# powersupppy.net
KiCad netlist of a schematic drawn in EAGLE
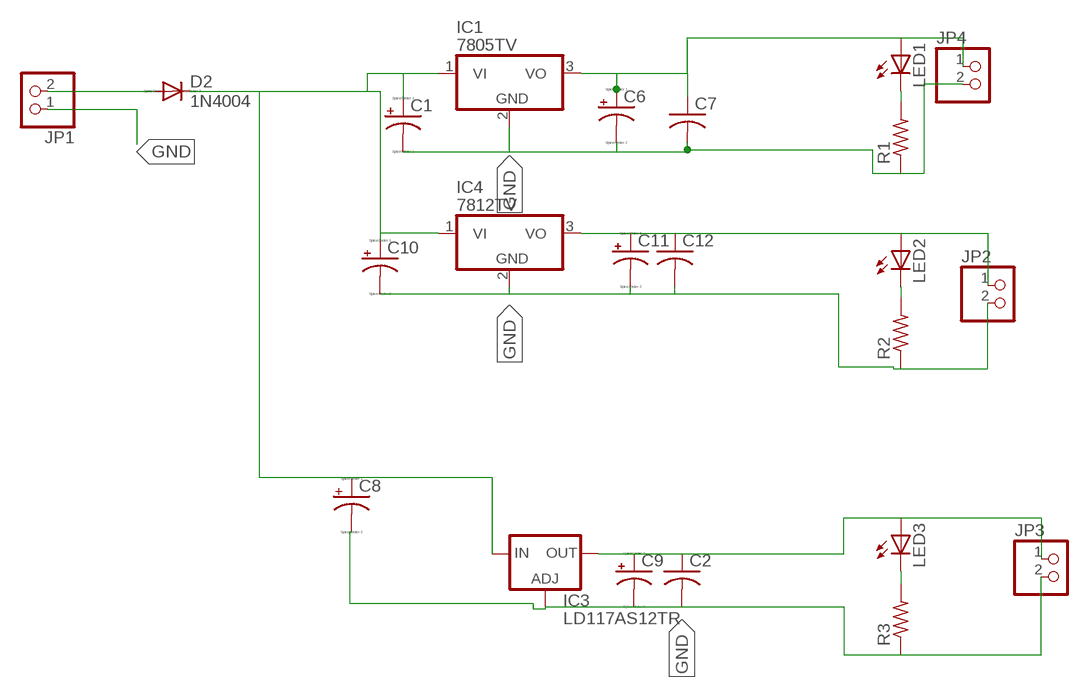
[diagram p0: schematic, sheet 1]

(export (version "E")
  (design (tool "Eeschema 10.0.6"))
  (components
    (comp (ref "C1")
      (value "CPOL-USE2.5-5")
      (footprint "eagle-import:E2,5-5")
      (libsource (lib "eagle-import") (part "CPOL-USE2.5-5"))
    )
    (comp (ref "C2")
      (value "C-US050-025X075")
      (footprint "eagle-import:C050-025X075")
      (libsource (lib "eagle-import") (part "C-US050-025X075"))
    )
    (comp (ref "C6")
      (value "CPOL-USE2.5-5")
      (footprint "eagle-import:E2,5-5")
      (libsource (lib "eagle-import") (part "CPOL-USE2.5-5"))
    )
    (comp (ref "C7")
      (value "C-US050-025X075")
      (footprint "eagle-import:C050-025X075")
      (libsource (lib "eagle-import") (part "C-US050-025X075"))
    )
    (comp (ref "C8")
      (value "CPOL-USE2.5-5")
      (footprint "eagle-import:E2,5-5")
      (libsource (lib "eagle-import") (part "CPOL-USE2.5-5"))
    )
    (comp (ref "C9")
      (value "CPOL-USE2.5-5")
      (footprint "eagle-import:E2,5-5")
      (libsource (lib "eagle-import") (part "CPOL-USE2.5-5"))
    )
    (comp (ref "C10")
      (value "CPOL-USE2.5-5")
      (footprint "eagle-import:E2,5-5")
      (libsource (lib "eagle-import") (part "CPOL-USE2.5-5"))
    )
    (comp (ref "C11")
      (value "CPOL-USE2.5-5")
      (footprint "eagle-import:E2,5-5")
      (libsource (lib "eagle-import") (part "CPOL-USE2.5-5"))
    )
    (comp (ref "C12")
      (value "C-US050-025X075")
      (footprint "eagle-import:C050-025X075")
      (libsource (lib "eagle-import") (part "C-US050-025X075"))
    )
    (comp (ref "D2")
      (value "1N4004")
      (footprint "eagle-import:DO41-10")
      (libsource (lib "eagle-import") (part "1N4004"))
    )
    (comp (ref "IC1")
      (value "7805TV")
      (footprint "eagle-import:TO220V")
      (libsource (lib "eagle-import") (part "78TV05"))
    )
    (comp (ref "IC3")
      (value "LD117AS12TR")
      (footprint "eagle-import:SOT223")
      (libsource (lib "eagle-import") (part "LD117A?S12TR"))
    )
    (comp (ref "IC4")
      (value "7812TV")
      (footprint "eagle-import:TO220V")
      (libsource (lib "eagle-import") (part "78TV12"))
    )
    (comp (ref "JP1")
      (value "PINHD-1X2")
      (footprint "eagle-import:1X02")
      (libsource (lib "eagle-import") (part "PINHD-1X2"))
    )
    (comp (ref "JP2")
      (value "PINHD-1X2")
      (footprint "eagle-import:1X02")
      (libsource (lib "eagle-import") (part "PINHD-1X2"))
    )
    (comp (ref "JP3")
      (value "PINHD-1X2")
      (footprint "eagle-import:1X02")
      (libsource (lib "eagle-import") (part "PINHD-1X2"))
    )
    (comp (ref "JP4")
      (value "PINHD-1X2")
      (footprint "eagle-import:1X02")
      (libsource (lib "eagle-import") (part "PINHD-1X2"))
    )
    (comp (ref "LED1")
      (value "LED3MM")
      (footprint "eagle-import:LED3MM")
      (libsource (lib "eagle-import") (part "LED3MM"))
    )
    (comp (ref "LED2")
      (value "LED3MM")
      (footprint "eagle-import:LED3MM")
      (libsource (lib "eagle-import") (part "LED3MM"))
    )
    (comp (ref "LED3")
      (value "LED3MM")
      (footprint "eagle-import:LED3MM")
      (libsource (lib "eagle-import") (part "LED3MM"))
    )
    (comp (ref "R1")
      (value "R-US_0207/10")
      (footprint "eagle-import:0207_10")
      (libsource (lib "eagle-import") (part "R-US_0207/10"))
    )
    (comp (ref "R2")
      (value "R-US_0207/10")
      (footprint "eagle-import:0207_10")
      (libsource (lib "eagle-import") (part "R-US_0207/10"))
    )
    (comp (ref "R3")
      (value "R-US_R1206")
      (footprint "eagle-import:R1206")
      (libsource (lib "eagle-import") (part "R-US_R1206"))
    )
  )
  (nets
    (net (code "1") (name "GND") (class "Default")
      (node (ref "C1") (pin "-") (pinfunction "-_-") (pintype "passive"))
      (node (ref "C10") (pin "-") (pinfunction "-_-") (pintype "passive"))
      (node (ref "C11") (pin "-") (pinfunction "-_-") (pintype "passive"))
      (node (ref "C12") (pin "2") (pinfunction "2_2") (pintype "passive"))
      (node (ref "C2") (pin "2") (pinfunction "2_2") (pintype "passive"))
      (node (ref "C6") (pin "-") (pinfunction "-_-") (pintype "passive"))
      (node (ref "C7") (pin "2") (pinfunction "2_2") (pintype "passive"))
      (node (ref "C8") (pin "-") (pinfunction "-_-") (pintype "passive"))
      (node (ref "C9") (pin "-") (pinfunction "-_-") (pintype "passive"))
      (node (ref "IC1") (pin "2") (pinfunction "GND_2") (pintype "passive"))
      (node (ref "IC3") (pin "1") (pinfunction "ADJ_1") (pintype "input"))
      (node (ref "IC4") (pin "2") (pinfunction "GND_2") (pintype "passive"))
      (node (ref "JP1") (pin "1") (pinfunction "1_1") (pintype "passive"))
      (node (ref "JP2") (pin "2") (pinfunction "2_2") (pintype "passive"))
      (node (ref "JP3") (pin "2") (pinfunction "2_2") (pintype "passive"))
      (node (ref "JP4") (pin "2") (pinfunction "2_2") (pintype "passive"))
      (node (ref "R1") (pin "1") (pinfunction "1_1") (pintype "passive"))
      (node (ref "R2") (pin "1") (pinfunction "1_1") (pintype "passive"))
      (node (ref "R3") (pin "1") (pinfunction "1_1") (pintype "passive"))
    )
    (net (code "2") (name "Net-(D2-PadA)") (class "Default")
      (node (ref "D2") (pin "A") (pinfunction "A_A") (pintype "passive"))
      (node (ref "JP1") (pin "2") (pinfunction "2_2") (pintype "passive"))
    )
    (net (code "3") (name "Net-(IC1-VI)") (class "Default")
      (node (ref "C1") (pin "+") (pinfunction "+_+") (pintype "passive"))
      (node (ref "C10") (pin "+") (pinfunction "+_+") (pintype "passive"))
      (node (ref "C8") (pin "+") (pinfunction "+_+") (pintype "passive"))
      (node (ref "D2") (pin "C") (pinfunction "C_C") (pintype "passive"))
      (node (ref "IC1") (pin "1") (pinfunction "VI_1") (pintype "input"))
      (node (ref "IC3") (pin "3") (pinfunction "IN_3") (pintype "input"))
      (node (ref "IC4") (pin "1") (pinfunction "VI_1") (pintype "input"))
    )
    (net (code "4") (name "Net-(IC1-VO)") (class "Default")
      (node (ref "C6") (pin "+") (pinfunction "+_+") (pintype "passive"))
      (node (ref "C7") (pin "1") (pinfunction "1_1") (pintype "passive"))
      (node (ref "IC1") (pin "3") (pinfunction "VO_3") (pintype "passive"))
      (node (ref "JP4") (pin "1") (pinfunction "1_1") (pintype "passive"))
      (node (ref "LED1") (pin "A") (pinfunction "A_A") (pintype "passive"))
    )
    (net (code "5") (name "Net-(IC3-OUT)") (class "Default")
      (node (ref "C2") (pin "1") (pinfunction "1_1") (pintype "passive"))
      (node (ref "C9") (pin "+") (pinfunction "+_+") (pintype "passive"))
      (node (ref "IC3") (pin "4") (pinfunction "OUT_4") (pintype "passive"))
      (node (ref "JP3") (pin "1") (pinfunction "1_1") (pintype "passive"))
      (node (ref "LED3") (pin "A") (pinfunction "A_A") (pintype "passive"))
    )
    (net (code "6") (name "Net-(IC4-VO)") (class "Default")
      (node (ref "C11") (pin "+") (pinfunction "+_+") (pintype "passive"))
      (node (ref "C12") (pin "1") (pinfunction "1_1") (pintype "passive"))
      (node (ref "IC4") (pin "3") (pinfunction "VO_3") (pintype "passive"))
      (node (ref "JP2") (pin "1") (pinfunction "1_1") (pintype "passive"))
      (node (ref "LED2") (pin "A") (pinfunction "A_A") (pintype "passive"))
    )
    (net (code "7") (name "Net-(LED1-C)") (class "Default")
      (node (ref "LED1") (pin "K") (pinfunction "C_K") (pintype "passive"))
      (node (ref "R1") (pin "2") (pinfunction "2_2") (pintype "passive"))
    )
    (net (code "8") (name "Net-(LED2-C)") (class "Default")
      (node (ref "LED2") (pin "K") (pinfunction "C_K") (pintype "passive"))
      (node (ref "R2") (pin "2") (pinfunction "2_2") (pintype "passive"))
    )
    (net (code "9") (name "Net-(LED3-C)") (class "Default")
      (node (ref "LED3") (pin "K") (pinfunction "C_K") (pintype "passive"))
      (node (ref "R3") (pin "2") (pinfunction "2_2") (pintype "passive"))
    )
  )
)
